# mapesynth_2pag.net
KiCad netlist of a schematic drawn in EAGLE
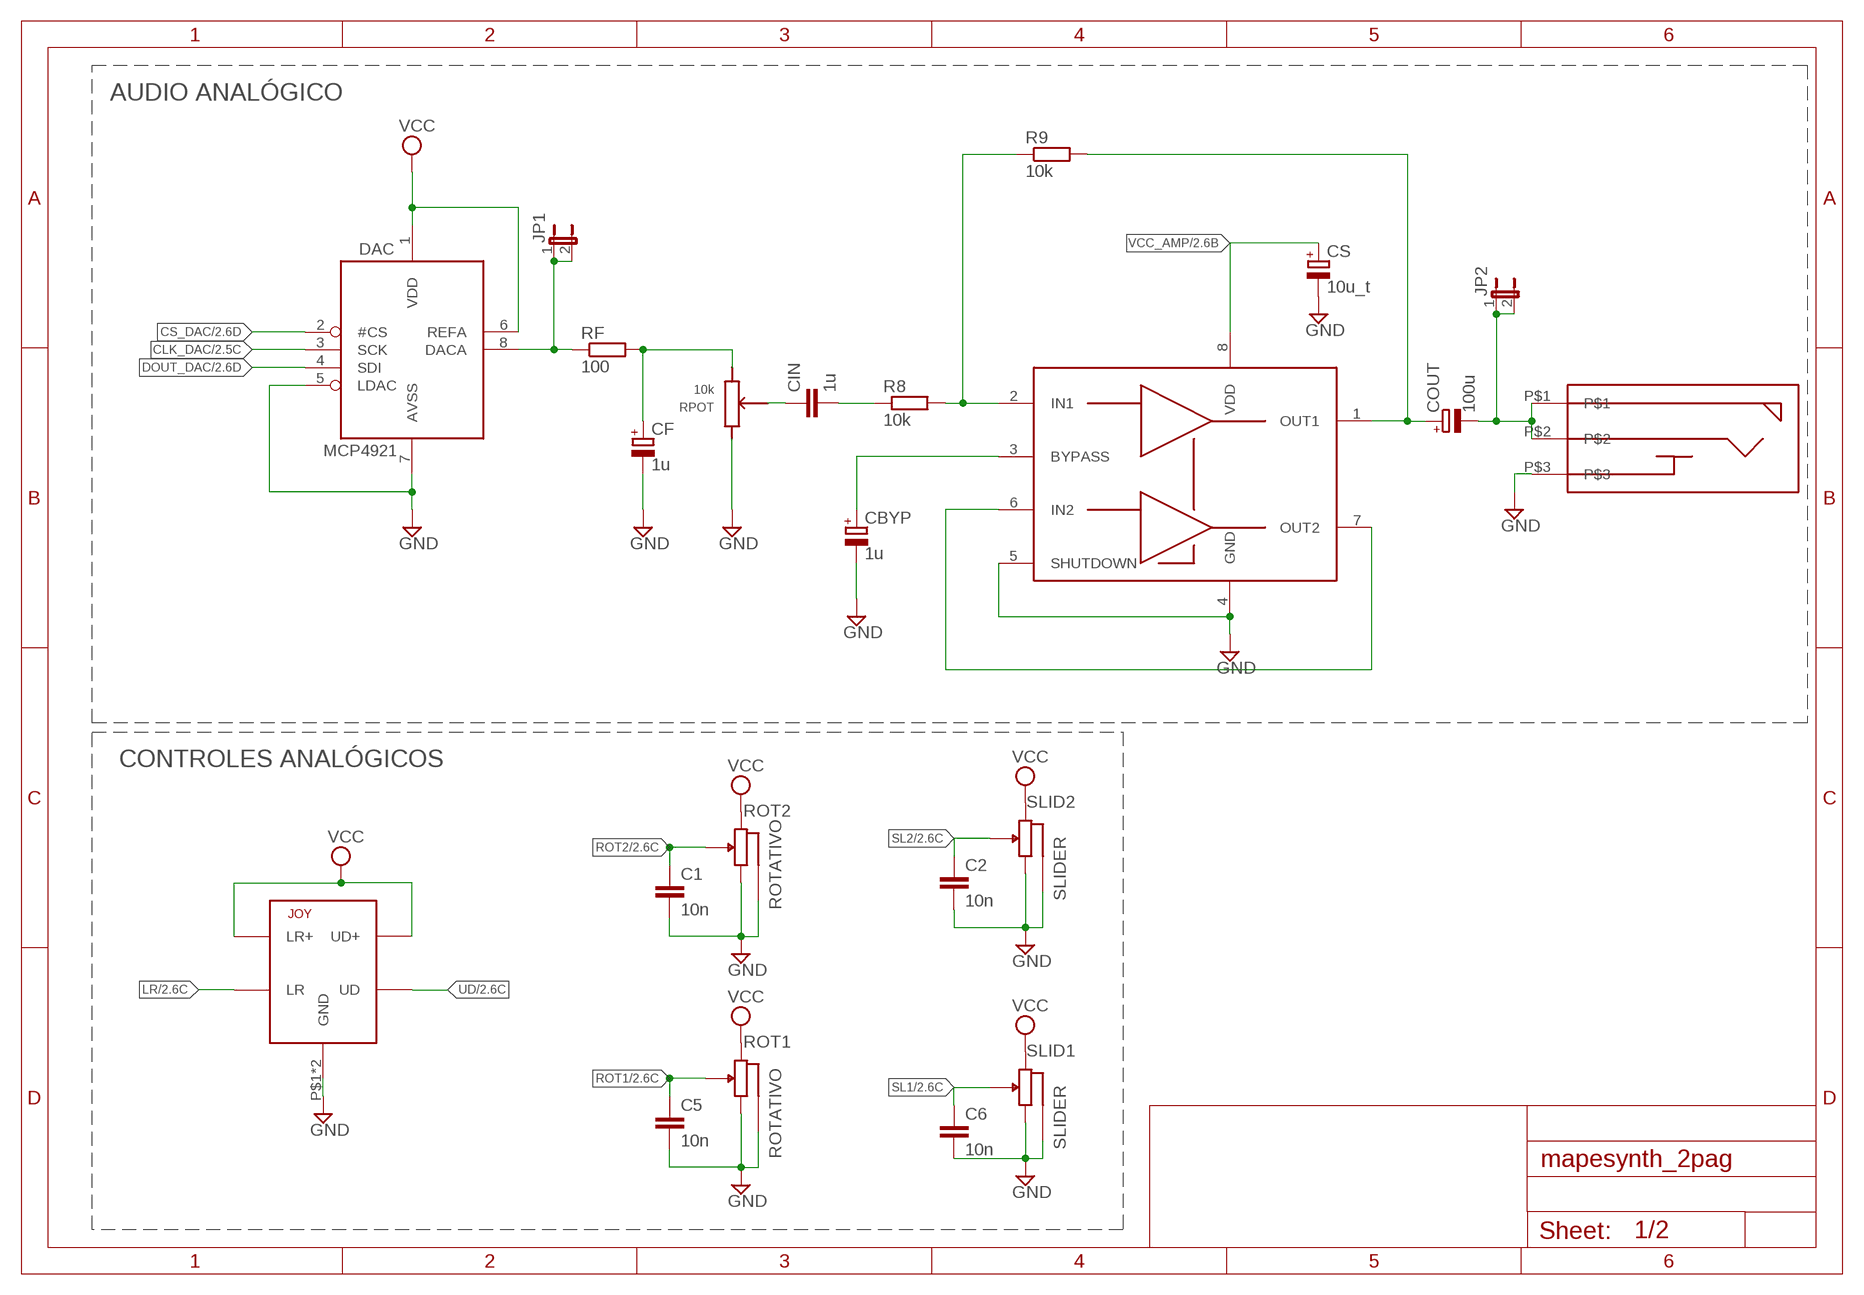
[diagram p0: schematic, sheet 1]
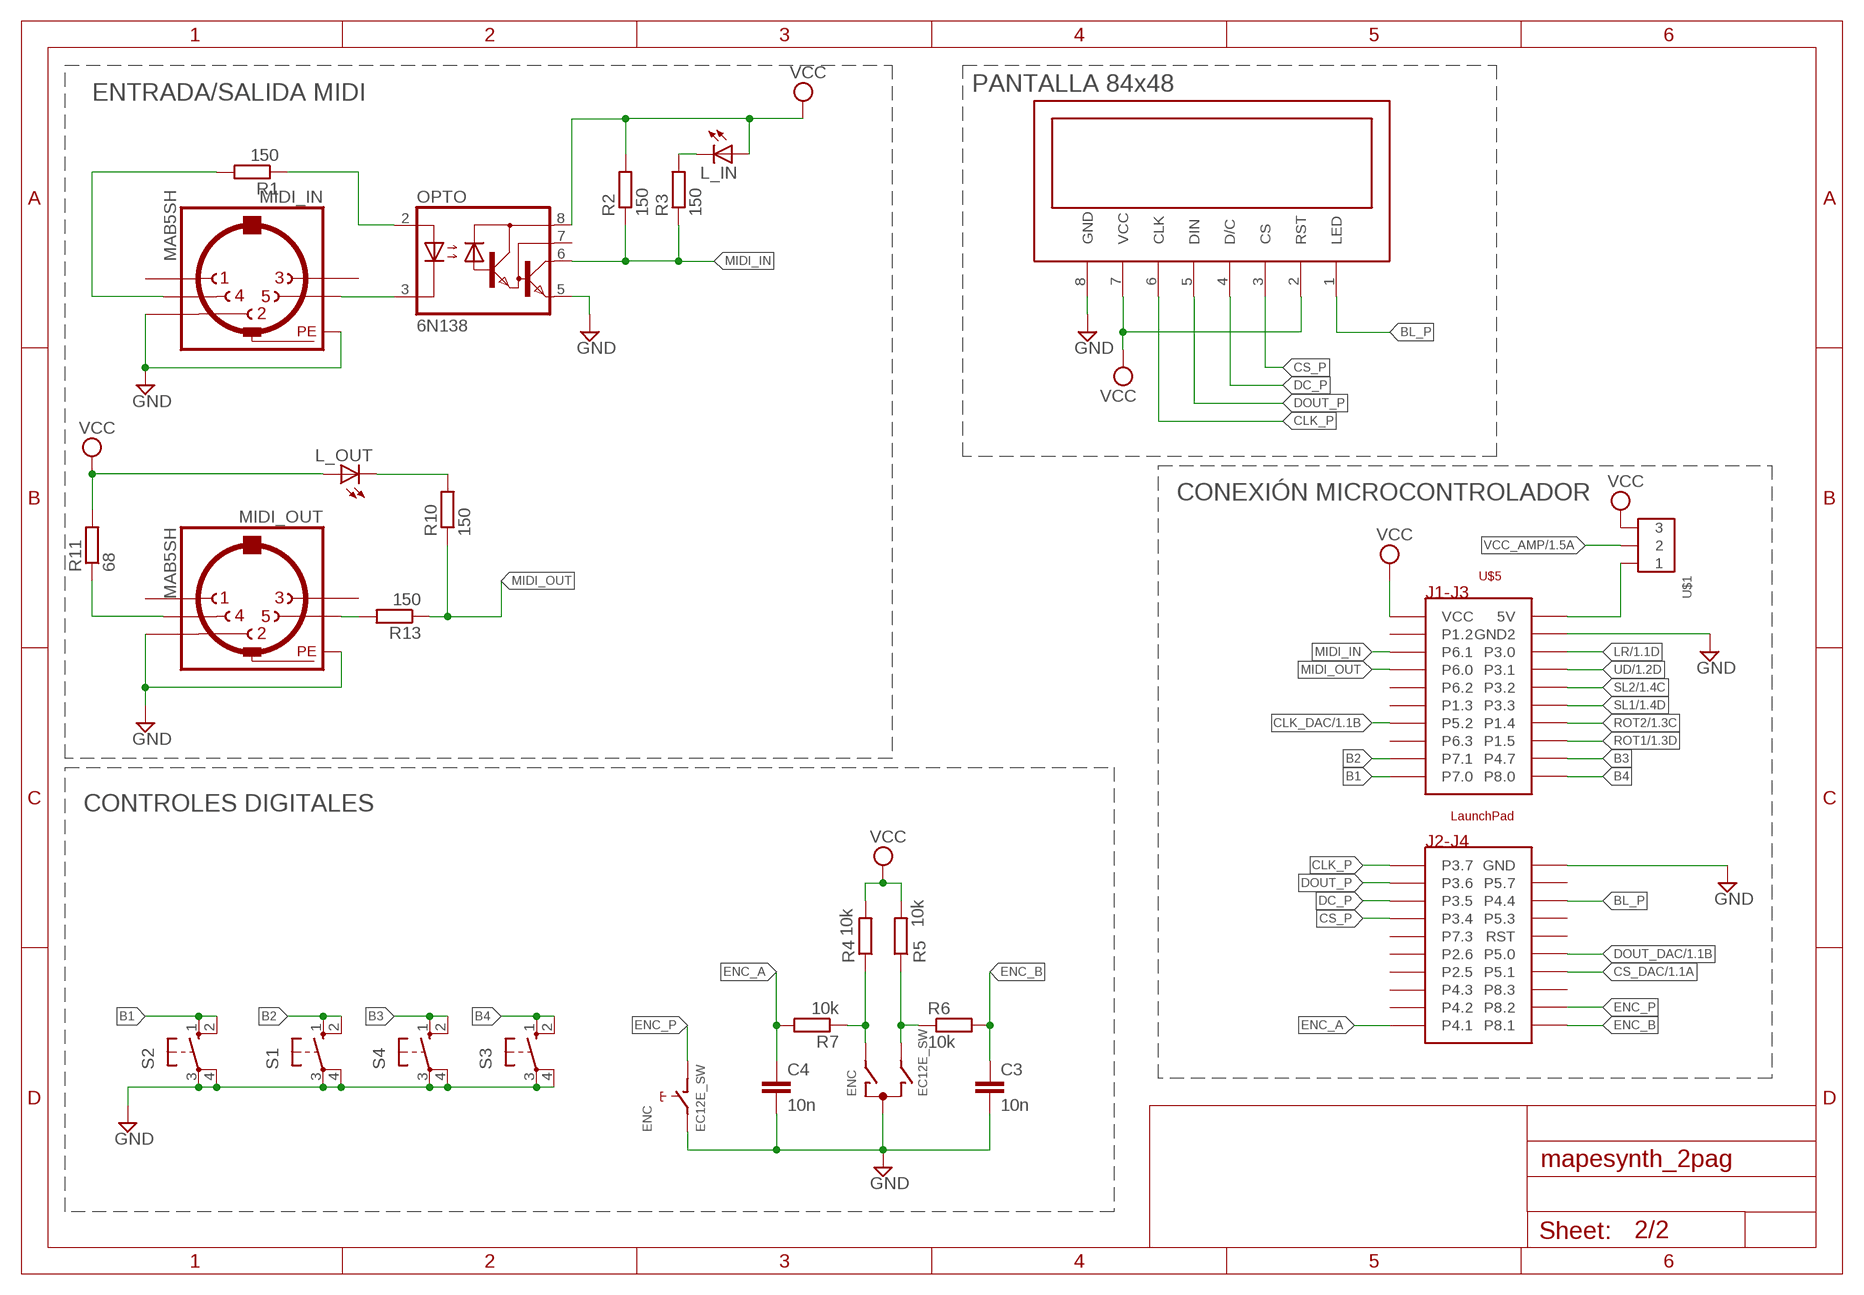
[diagram p1: schematic, sheet 2]

(export (version "E")
  (design (tool "Eeschema 10.0.6"))
  (components
    (comp (ref "C3")
      (value "10n")
      (footprint "eagle-import:C050-024X044")
      (libsource (lib "eagle-import") (part "rcl_C-EU050-024X044"))
    )
    (comp (ref "C4")
      (value "10n")
      (footprint "eagle-import:C050-024X044")
      (libsource (lib "eagle-import") (part "rcl_C-EU050-024X044"))
    )
    (comp (ref "ENC")
      (value "EC12E_SW")
      (footprint "eagle-import:ALPS_EC12E_SW")
      (fields (field (name "MPN") "EC12E2424407"))
      (libsource (lib "eagle-import") (part "EC12E_SW"))
    )
    (comp (ref "L_IN")
      (value "LED5MM")
      (footprint "eagle-import:LED5MM")
      (libsource (lib "eagle-import") (part "LED5MM"))
    )
    (comp (ref "L_OUT")
      (value "LED5MM")
      (footprint "eagle-import:LED5MM")
      (libsource (lib "eagle-import") (part "LED5MM"))
    )
    (comp (ref "MIDI_IN")
      (value "MAB5SH")
      (footprint "eagle-import:MAB5SH")
      (libsource (lib "eagle-import") (part "MAB5SH"))
    )
    (comp (ref "MIDI_OUT")
      (value "MAB5SH")
      (footprint "eagle-import:MAB5SH")
      (libsource (lib "eagle-import") (part "MAB5SH"))
    )
    (comp (ref "OPTO")
      (value "6N138")
      (footprint "eagle-import:DIL08")
      (fields (field (name "MF") "VISHAY/TELEFUNKEN"))
      (libsource (lib "eagle-import") (part "6N138"))
    )
    (comp (ref "R1")
      (value "150")
      (footprint "eagle-import:0207_10")
      (libsource (lib "eagle-import") (part "resistor_R-EU_0207/10"))
    )
    (comp (ref "R2")
      (value "150")
      (footprint "eagle-import:0207_10")
      (libsource (lib "eagle-import") (part "resistor_R-EU_0207/10"))
    )
    (comp (ref "R3")
      (value "150")
      (footprint "eagle-import:0207_10")
      (libsource (lib "eagle-import") (part "resistor_R-EU_0207/10"))
    )
    (comp (ref "R4")
      (value "10k")
      (footprint "eagle-import:R1206")
      (libsource (lib "eagle-import") (part "R-EU_R1206"))
    )
    (comp (ref "R5")
      (value "10k")
      (footprint "eagle-import:R1206")
      (libsource (lib "eagle-import") (part "R-EU_R1206"))
    )
    (comp (ref "R6")
      (value "10k")
      (footprint "eagle-import:R1206")
      (libsource (lib "eagle-import") (part "R-EU_R1206"))
    )
    (comp (ref "R7")
      (value "10k")
      (footprint "eagle-import:R1206")
      (libsource (lib "eagle-import") (part "R-EU_R1206"))
    )
    (comp (ref "R10")
      (value "150")
      (footprint "eagle-import:0207_10")
      (libsource (lib "eagle-import") (part "resistor_R-EU_0207/10"))
    )
    (comp (ref "R11")
      (value "68")
      (footprint "eagle-import:0207_10")
      (libsource (lib "eagle-import") (part "resistor_R-EU_0207/10"))
    )
    (comp (ref "R13")
      (value "150")
      (footprint "eagle-import:0207_10")
      (libsource (lib "eagle-import") (part "resistor_R-EU_0207/10"))
    )
    (comp (ref "S1")
      (value "40-XX")
      (footprint "eagle-import:B3F-40XX")
      (fields (field (name "MF") "OMRON COMPONENTS USA") (field (name "MPN") "B3F-4000"))
      (libsource (lib "eagle-import") (part "40-XX"))
    )
    (comp (ref "S2")
      (value "40-XX")
      (footprint "eagle-import:B3F-40XX")
      (fields (field (name "MF") "OMRON COMPONENTS USA") (field (name "MPN") "B3F-4000"))
      (libsource (lib "eagle-import") (part "40-XX"))
    )
    (comp (ref "S3")
      (value "40-XX")
      (footprint "eagle-import:B3F-40XX")
      (fields (field (name "MF") "OMRON COMPONENTS USA") (field (name "MPN") "B3F-4000"))
      (libsource (lib "eagle-import") (part "40-XX"))
    )
    (comp (ref "S4")
      (value "40-XX")
      (footprint "eagle-import:B3F-40XX")
      (fields (field (name "MF") "OMRON COMPONENTS USA") (field (name "MPN") "B3F-4000"))
      (libsource (lib "eagle-import") (part "40-XX"))
    )
    (comp (ref "U$1")
      (value "JP3")
      (footprint "eagle-import:JP3")
      (libsource (lib "eagle-import") (part "JP3"))
    )
    (comp (ref "U$3")
      (value "NOKIA_5110")
      (footprint "eagle-import:NOKIA_5110")
      (libsource (lib "eagle-import") (part "NOKIA_5110"))
    )
    (comp (ref "U$5")
      (value "LAUNCHPAD_XL")
      (footprint "eagle-import:LAUNCHPAD_XL")
      (libsource (lib "eagle-import") (part "LAUNCHPAD_XL"))
    )
    (comp (ref "AMP")
      (value "TPA6111")
      (footprint "eagle-import:SO-08")
      (libsource (lib "eagle-import") (part "TPA6111"))
    )
    (comp (ref "C1")
      (value "10n")
      (footprint "eagle-import:C050-024X044")
      (libsource (lib "eagle-import") (part "rcl_C-EU050-024X044"))
    )
    (comp (ref "C2")
      (value "10n")
      (footprint "eagle-import:C050-024X044")
      (libsource (lib "eagle-import") (part "rcl_C-EU050-024X044"))
    )
    (comp (ref "C5")
      (value "10n")
      (footprint "eagle-import:C050-024X044")
      (libsource (lib "eagle-import") (part "rcl_C-EU050-024X044"))
    )
    (comp (ref "C6")
      (value "10n")
      (footprint "eagle-import:C050-024X044")
      (libsource (lib "eagle-import") (part "rcl_C-EU050-024X044"))
    )
    (comp (ref "CBYP")
      (value "1u")
      (footprint "eagle-import:153CLV-0405")
      (libsource (lib "eagle-import") (part "CPOL-EU153CLV-0405"))
    )
    (comp (ref "CF")
      (value "1u")
      (footprint "eagle-import:153CLV-0405")
      (libsource (lib "eagle-import") (part "CPOL-EU153CLV-0405"))
    )
    (comp (ref "CIN")
      (value "1u")
      (footprint "eagle-import:C1206")
      (libsource (lib "eagle-import") (part "C-EUC1206"))
    )
    (comp (ref "COUT")
      (value "100u")
      (footprint "eagle-import:153CLV-0605")
      (libsource (lib "eagle-import") (part "CPOL-EU153CLV-0605"))
    )
    (comp (ref "CS")
      (value "10u_t")
      (footprint "eagle-import:CT3528")
      (libsource (lib "eagle-import") (part "CPOL-EUCT3528"))
    )
    (comp (ref "DAC")
      (value "MCP4921EN_SMD")
      (footprint "eagle-import:SO-08")
      (libsource (lib "eagle-import") (part "MCP4921EN_SMD"))
    )
    (comp (ref "JOY")
      (value "JOYSTICK")
      (footprint "eagle-import:PLACAJSTICK")
      (libsource (lib "eagle-import") (part "JOYSTICK"))
    )
    (comp (ref "JP1")
      (value "JP1E")
      (footprint "eagle-import:JP1")
      (libsource (lib "eagle-import") (part "JP1E"))
    )
    (comp (ref "JP2")
      (value "JP1E")
      (footprint "eagle-import:JP1")
      (libsource (lib "eagle-import") (part "JP1E"))
    )
    (comp (ref "R8")
      (value "10k")
      (footprint "eagle-import:M1206")
      (libsource (lib "eagle-import") (part "rcl_R-EU_M1206"))
    )
    (comp (ref "R9")
      (value "10k")
      (footprint "eagle-import:M1206")
      (libsource (lib "eagle-import") (part "rcl_R-EU_M1206"))
    )
    (comp (ref "RF")
      (value "100")
      (footprint "eagle-import:M1206")
      (libsource (lib "eagle-import") (part "rcl_R-EU_M1206"))
    )
    (comp (ref "ROT1")
      (value "ROTATIVO")
      (footprint "eagle-import:ROTATIVO")
      (libsource (lib "eagle-import") (part "ROTATIVO"))
    )
    (comp (ref "ROT2")
      (value "ROTATIVO")
      (footprint "eagle-import:ROTATIVO")
      (libsource (lib "eagle-import") (part "ROTATIVO"))
    )
    (comp (ref "RPOT")
      (value "10k")
      (footprint "eagle-import:POT_VOL")
      (libsource (lib "eagle-import") (part "POT_VOL"))
    )
    (comp (ref "SLID1")
      (value "SLIDER")
      (footprint "eagle-import:SLIDER")
      (libsource (lib "eagle-import") (part "SLIDER"))
    )
    (comp (ref "SLID2")
      (value "SLIDER")
      (footprint "eagle-import:SLIDER")
      (libsource (lib "eagle-import") (part "SLIDER"))
    )
    (comp (ref "U$4")
      (value "JACK_3_5MM_VA")
      (footprint "eagle-import:JACK3_5MM_V2")
      (libsource (lib "eagle-import") (part "JACK_3_5MM_VA"))
    )
  )
  (nets
    (net (code "1") (name "B1") (class "Default")
      (node (ref "S2") (pin "1") (pinfunction "S_1") (pintype "passive"))
      (node (ref "S2") (pin "2") (pinfunction "S1_2") (pintype "passive"))
      (node (ref "U$5") (pin "P$10") (pinfunction "P7.0_P$10") (pintype "bidirectional"))
    )
    (net (code "2") (name "B2") (class "Default")
      (node (ref "S1") (pin "1") (pinfunction "S_1") (pintype "passive"))
      (node (ref "S1") (pin "2") (pinfunction "S1_2") (pintype "passive"))
      (node (ref "U$5") (pin "P$9") (pinfunction "P7.1_P$9") (pintype "bidirectional"))
    )
    (net (code "3") (name "B3") (class "Default")
      (node (ref "S4") (pin "1") (pinfunction "S_1") (pintype "passive"))
      (node (ref "S4") (pin "2") (pinfunction "S1_2") (pintype "passive"))
      (node (ref "U$5") (pin "P$29") (pinfunction "P4.7_P$29") (pintype "bidirectional"))
    )
    (net (code "4") (name "B4") (class "Default")
      (node (ref "S3") (pin "1") (pinfunction "S_1") (pintype "passive"))
      (node (ref "S3") (pin "2") (pinfunction "S1_2") (pintype "passive"))
      (node (ref "U$5") (pin "P$30") (pinfunction "P8.0_P$30") (pintype "bidirectional"))
    )
    (net (code "5") (name "BL_P") (class "Default")
      (node (ref "U$3") (pin "1") (pinfunction "LED_1") (pintype "bidirectional"))
      (node (ref "U$5") (pin "P$18") (pinfunction "P4.4_P$18") (pintype "bidirectional"))
    )
    (net (code "6") (name "CLK_DAC") (class "Default")
      (node (ref "DAC") (pin "3") (pinfunction "SCK_3") (pintype "input"))
      (node (ref "U$5") (pin "P$7") (pinfunction "P5.2_P$7") (pintype "bidirectional"))
    )
    (net (code "7") (name "CLK_P") (class "Default")
      (node (ref "U$3") (pin "6") (pinfunction "CLK_6") (pintype "bidirectional"))
      (node (ref "U$5") (pin "P$40") (pinfunction "P3.7_P$40") (pintype "bidirectional"))
    )
    (net (code "8") (name "CS_DAC") (class "Default")
      (node (ref "DAC") (pin "2") (pinfunction "#CS_2") (pintype "input"))
      (node (ref "U$5") (pin "P$14") (pinfunction "P5.1_P$14") (pintype "bidirectional"))
    )
    (net (code "9") (name "CS_P") (class "Default")
      (node (ref "U$3") (pin "3") (pinfunction "CS_3") (pintype "bidirectional"))
      (node (ref "U$5") (pin "P$37") (pinfunction "P3.4_P$37") (pintype "bidirectional"))
    )
    (net (code "10") (name "DC_P") (class "Default")
      (node (ref "U$3") (pin "4") (pinfunction "D/C_4") (pintype "bidirectional"))
      (node (ref "U$5") (pin "P$38") (pinfunction "P3.5_P$38") (pintype "bidirectional"))
    )
    (net (code "11") (name "DOUT_DAC") (class "Default")
      (node (ref "DAC") (pin "4") (pinfunction "SDI_4") (pintype "input"))
      (node (ref "U$5") (pin "P$15") (pinfunction "P5.0_P$15") (pintype "bidirectional"))
    )
    (net (code "12") (name "DOUT_P") (class "Default")
      (node (ref "U$3") (pin "5") (pinfunction "DIN_5") (pintype "bidirectional"))
      (node (ref "U$5") (pin "P$39") (pinfunction "P3.6_P$39") (pintype "bidirectional"))
    )
    (net (code "13") (name "ENC_A") (class "Default")
      (node (ref "C4") (pin "1") (pinfunction "1_1") (pintype "passive"))
      (node (ref "R7") (pin "2") (pinfunction "2_2") (pintype "passive"))
      (node (ref "U$5") (pin "P$31") (pinfunction "P4.1_P$31") (pintype "bidirectional"))
    )
    (net (code "14") (name "ENC_B") (class "Default")
      (node (ref "C3") (pin "1") (pinfunction "1_1") (pintype "passive"))
      (node (ref "R6") (pin "2") (pinfunction "2_2") (pintype "passive"))
      (node (ref "U$5") (pin "P$11") (pinfunction "P8.1_P$11") (pintype "bidirectional"))
    )
    (net (code "15") (name "ENC_P") (class "Default")
      (node (ref "ENC") (pin "D") (pinfunction "1_D") (pintype "passive"))
      (node (ref "U$5") (pin "P$12") (pinfunction "P8.2_P$12") (pintype "bidirectional"))
    )
    (net (code "16") (name "GND") (class "Default")
      (node (ref "AMP") (pin "4") (pinfunction "GND_4") (pintype "bidirectional"))
      (node (ref "AMP") (pin "5") (pinfunction "SHUTDOWN_5") (pintype "bidirectional"))
      (node (ref "C1") (pin "2") (pinfunction "2_2") (pintype "passive"))
      (node (ref "C2") (pin "2") (pinfunction "2_2") (pintype "passive"))
      (node (ref "C3") (pin "2") (pinfunction "2_2") (pintype "passive"))
      (node (ref "C4") (pin "2") (pinfunction "2_2") (pintype "passive"))
      (node (ref "C5") (pin "2") (pinfunction "2_2") (pintype "passive"))
      (node (ref "C6") (pin "2") (pinfunction "2_2") (pintype "passive"))
      (node (ref "CBYP") (pin "-") (pinfunction "-_-") (pintype "passive"))
      (node (ref "CF") (pin "-") (pinfunction "-_-") (pintype "passive"))
      (node (ref "CS") (pin "-") (pinfunction "-_-") (pintype "passive"))
      (node (ref "DAC") (pin "5") (pinfunction "LDAC_5") (pintype "input"))
      (node (ref "DAC") (pin "7") (pinfunction "AVSS_7") (pintype "power_in"))
      (node (ref "ENC") (pin "C") (pinfunction "C_C") (pintype "passive"))
      (node (ref "ENC") (pin "E") (pinfunction "2_E") (pintype "passive"))
      (node (ref "JOY") (pin "P$1") (pinfunction "GND_P$1") (pintype "bidirectional"))
      (node (ref "JOY") (pin "P$8") (pinfunction "GND_P$8") (pintype "bidirectional"))
      (node (ref "MIDI_IN") (pin "2") (pinfunction "2_2") (pintype "passive"))
      (node (ref "MIDI_IN") (pin "PE") (pinfunction "PE_PE") (pintype "power_in"))
      (node (ref "MIDI_IN") (pin "PE@") (pinfunction "PE_PE@") (pintype "power_in"))
      (node (ref "MIDI_OUT") (pin "2") (pinfunction "2_2") (pintype "passive"))
      (node (ref "MIDI_OUT") (pin "PE") (pinfunction "PE_PE") (pintype "power_in"))
      (node (ref "MIDI_OUT") (pin "PE@") (pinfunction "PE_PE@") (pintype "power_in"))
      (node (ref "OPTO") (pin "5") (pinfunction "GND_5") (pintype "passive"))
      (node (ref "ROT1") (pin "A") (pinfunction "1_A") (pintype "passive"))
      (node (ref "ROT1") (pin "GND1") (pinfunction "GND_GND1") (pintype "bidirectional"))
      (node (ref "ROT1") (pin "GND2") (pinfunction "GND_GND2") (pintype "bidirectional"))
      (node (ref "ROT2") (pin "A") (pinfunction "1_A") (pintype "passive"))
      (node (ref "ROT2") (pin "GND1") (pinfunction "GND_GND1") (pintype "bidirectional"))
      (node (ref "ROT2") (pin "GND2") (pinfunction "GND_GND2") (pintype "bidirectional"))
      (node (ref "RPOT") (pin "P$1") (pinfunction "P$1_P$1") (pintype "bidirectional"))
      (node (ref "S1") (pin "3") (pinfunction "P_3") (pintype "passive"))
      (node (ref "S1") (pin "4") (pinfunction "P1_4") (pintype "passive"))
      (node (ref "S2") (pin "3") (pinfunction "P_3") (pintype "passive"))
      (node (ref "S2") (pin "4") (pinfunction "P1_4") (pintype "passive"))
      (node (ref "S3") (pin "3") (pinfunction "P_3") (pintype "passive"))
      (node (ref "S3") (pin "4") (pinfunction "P1_4") (pintype "passive"))
      (node (ref "S4") (pin "3") (pinfunction "P_3") (pintype "passive"))
      (node (ref "S4") (pin "4") (pinfunction "P1_4") (pintype "passive"))
      (node (ref "SLID1") (pin "1") (pinfunction "1_1") (pintype "passive"))
      (node (ref "SLID1") (pin "4") (pinfunction "GND_4") (pintype "bidirectional"))
      (node (ref "SLID1") (pin "5") (pinfunction "GND_5") (pintype "bidirectional"))
      (node (ref "SLID1") (pin "6") (pinfunction "GND_6") (pintype "bidirectional"))
      (node (ref "SLID1") (pin "7") (pinfunction "GND_7") (pintype "bidirectional"))
      (node (ref "SLID2") (pin "1") (pinfunction "1_1") (pintype "passive"))
      (node (ref "SLID2") (pin "4") (pinfunction "GND_4") (pintype "bidirectional"))
      (node (ref "SLID2") (pin "5") (pinfunction "GND_5") (pintype "bidirectional"))
      (node (ref "SLID2") (pin "6") (pinfunction "GND_6") (pintype "bidirectional"))
      (node (ref "SLID2") (pin "7") (pinfunction "GND_7") (pintype "bidirectional"))
      (node (ref "U$3") (pin "8") (pinfunction "GND_8") (pintype "bidirectional"))
      (node (ref "U$4") (pin "P$3") (pinfunction "P$3_P$3") (pintype "bidirectional"))
      (node (ref "U$5") (pin "P$20") (pinfunction "GND_P$20") (pintype "bidirectional"))
      (node (ref "U$5") (pin "P$22") (pinfunction "GND2_P$22") (pintype "bidirectional"))
    )
    (net (code "17") (name "LR") (class "Default")
      (node (ref "JOY") (pin "P$3") (pinfunction "LR_P$3") (pintype "bidirectional"))
      (node (ref "JOY") (pin "P$6") (pinfunction "LR_P$6") (pintype "bidirectional"))
      (node (ref "U$5") (pin "P$23") (pinfunction "P3.0_P$23") (pintype "bidirectional"))
    )
    (net (code "18") (name "MIDI_IN") (class "Default")
      (node (ref "OPTO") (pin "6") (pinfunction "VO_6") (pintype "passive"))
      (node (ref "R2") (pin "1") (pinfunction "1_1") (pintype "passive"))
      (node (ref "R3") (pin "1") (pinfunction "1_1") (pintype "passive"))
      (node (ref "U$5") (pin "P$3") (pinfunction "P6.1_P$3") (pintype "bidirectional"))
    )
    (net (code "19") (name "MIDI_OUT") (class "Default")
      (node (ref "R10") (pin "1") (pinfunction "1_1") (pintype "passive"))
      (node (ref "R13") (pin "1") (pinfunction "1_1") (pintype "passive"))
      (node (ref "U$5") (pin "P$4") (pinfunction "P6.0_P$4") (pintype "bidirectional"))
    )
    (net (code "20") (name "Net-(AMP-BYPASS)") (class "Default")
      (node (ref "AMP") (pin "3") (pinfunction "BYPASS_3") (pintype "bidirectional"))
      (node (ref "CBYP") (pin "+") (pinfunction "+_+") (pintype "passive"))
    )
    (net (code "21") (name "Net-(AMP-IN1)") (class "Default")
      (node (ref "AMP") (pin "2") (pinfunction "IN1_2") (pintype "bidirectional"))
      (node (ref "R8") (pin "2") (pinfunction "2_2") (pintype "passive"))
      (node (ref "R9") (pin "1") (pinfunction "1_1") (pintype "passive"))
    )
    (net (code "22") (name "Net-(AMP-IN2)") (class "Default")
      (node (ref "AMP") (pin "6") (pinfunction "IN2_6") (pintype "bidirectional"))
      (node (ref "AMP") (pin "7") (pinfunction "OUT2_7") (pintype "bidirectional"))
    )
    (net (code "23") (name "Net-(AMP-OUT1)") (class "Default")
      (node (ref "AMP") (pin "1") (pinfunction "OUT1_1") (pintype "bidirectional"))
      (node (ref "COUT") (pin "+") (pinfunction "+_+") (pintype "passive"))
      (node (ref "R9") (pin "2") (pinfunction "2_2") (pintype "passive"))
    )
    (net (code "24") (name "Net-(CF-Pad+)") (class "Default")
      (node (ref "CF") (pin "+") (pinfunction "+_+") (pintype "passive"))
      (node (ref "RF") (pin "2") (pinfunction "2_2") (pintype "passive"))
      (node (ref "RPOT") (pin "P$3") (pinfunction "P$3_P$3") (pintype "bidirectional"))
    )
    (net (code "25") (name "Net-(CIN-Pad1)") (class "Default")
      (node (ref "CIN") (pin "1") (pinfunction "1_1") (pintype "passive"))
      (node (ref "RPOT") (pin "P$2") (pinfunction "P$2_P$2") (pintype "bidirectional"))
    )
    (net (code "26") (name "Net-(CIN-Pad2)") (class "Default")
      (node (ref "CIN") (pin "2") (pinfunction "2_2") (pintype "passive"))
      (node (ref "R8") (pin "1") (pinfunction "1_1") (pintype "passive"))
    )
    (net (code "27") (name "Net-(COUT-Pad-)") (class "Default")
      (node (ref "COUT") (pin "-") (pinfunction "-_-") (pintype "passive"))
      (node (ref "JP2") (pin "1") (pinfunction "1_1") (pintype "passive"))
      (node (ref "JP2") (pin "2") (pinfunction "2_2") (pintype "passive"))
      (node (ref "U$4") (pin "P$1") (pinfunction "P$1_P$1") (pintype "bidirectional"))
      (node (ref "U$4") (pin "P$2") (pinfunction "P$2_P$2") (pintype "bidirectional"))
    )
    (net (code "28") (name "Net-(DAC-DACA)") (class "Default")
      (node (ref "DAC") (pin "8") (pinfunction "DACA_8") (pintype "output"))
      (node (ref "JP1") (pin "1") (pinfunction "1_1") (pintype "passive"))
      (node (ref "JP1") (pin "2") (pinfunction "2_2") (pintype "passive"))
      (node (ref "RF") (pin "1") (pinfunction "1_1") (pintype "passive"))
    )
    (net (code "29") (name "Net-(ENC-PadA)") (class "Default")
      (node (ref "ENC") (pin "A") (pinfunction "A_A") (pintype "passive"))
      (node (ref "R4") (pin "1") (pinfunction "1_1") (pintype "passive"))
      (node (ref "R7") (pin "1") (pinfunction "1_1") (pintype "passive"))
    )
    (net (code "30") (name "Net-(ENC-PadB)") (class "Default")
      (node (ref "ENC") (pin "B") (pinfunction "B_B") (pintype "passive"))
      (node (ref "R5") (pin "1") (pinfunction "1_1") (pintype "passive"))
      (node (ref "R6") (pin "1") (pinfunction "1_1") (pintype "passive"))
    )
    (net (code "31") (name "Net-(L_IN-C)") (class "Default")
      (node (ref "L_IN") (pin "K") (pinfunction "C_K") (pintype "passive"))
      (node (ref "R3") (pin "2") (pinfunction "2_2") (pintype "passive"))
    )
    (net (code "32") (name "Net-(L_OUT-C)") (class "Default")
      (node (ref "L_OUT") (pin "K") (pinfunction "C_K") (pintype "passive"))
      (node (ref "R10") (pin "2") (pinfunction "2_2") (pintype "passive"))
    )
    (net (code "33") (name "Net-(MIDI_IN-Pad4)") (class "Default")
      (node (ref "MIDI_IN") (pin "4") (pinfunction "4_4") (pintype "passive"))
      (node (ref "R1") (pin "2") (pinfunction "2_2") (pintype "passive"))
    )
    (net (code "34") (name "Net-(MIDI_OUT-Pad4)") (class "Default")
      (node (ref "MIDI_OUT") (pin "4") (pinfunction "4_4") (pintype "passive"))
      (node (ref "R11") (pin "1") (pinfunction "1_1") (pintype "passive"))
    )
    (net (code "35") (name "Net-(MIDI_OUT-Pad5)") (class "Default")
      (node (ref "MIDI_OUT") (pin "5") (pinfunction "5_5") (pintype "passive"))
      (node (ref "R13") (pin "2") (pinfunction "2_2") (pintype "passive"))
    )
    (net (code "36") (name "Net-(OPTO-A)") (class "Default")
      (node (ref "OPTO") (pin "2") (pinfunction "A_2") (pintype "passive"))
      (node (ref "R1") (pin "1") (pinfunction "1_1") (pintype "passive"))
    )
    (net (code "37") (name "Net-(OPTO-C)") (class "Default")
      (node (ref "MIDI_IN") (pin "5") (pinfunction "5_5") (pintype "passive"))
      (node (ref "OPTO") (pin "3") (pinfunction "C_3") (pintype "passive"))
    )
    (net (code "38") (name "Net-(U$1-1)") (class "Default")
      (node (ref "U$1") (pin "P$1") (pinfunction "1_P$1") (pintype "bidirectional"))
      (node (ref "U$5") (pin "P$21") (pinfunction "5V_P$21") (pintype "bidirectional"))
    )
    (net (code "39") (name "ROT1") (class "Default")
      (node (ref "C5") (pin "1") (pinfunction "1_1") (pintype "passive"))
      (node (ref "ROT1") (pin "C") (pinfunction "2_C") (pintype "passive"))
      (node (ref "U$5") (pin "P$28") (pinfunction "P1.5_P$28") (pintype "bidirectional"))
    )
    (net (code "40") (name "ROT2") (class "Default")
      (node (ref "C1") (pin "1") (pinfunction "1_1") (pintype "passive"))
      (node (ref "ROT2") (pin "C") (pinfunction "2_C") (pintype "passive"))
      (node (ref "U$5") (pin "P$27") (pinfunction "P1.4_P$27") (pintype "bidirectional"))
    )
    (net (code "41") (name "SL1") (class "Default")
      (node (ref "C6") (pin "1") (pinfunction "1_1") (pintype "passive"))
      (node (ref "SLID1") (pin "2") (pinfunction "2_2") (pintype "passive"))
      (node (ref "U$5") (pin "P$26") (pinfunction "P3.3_P$26") (pintype "bidirectional"))
    )
    (net (code "42") (name "SL2") (class "Default")
      (node (ref "C2") (pin "1") (pinfunction "1_1") (pintype "passive"))
      (node (ref "SLID2") (pin "2") (pinfunction "2_2") (pintype "passive"))
      (node (ref "U$5") (pin "P$25") (pinfunction "P3.2_P$25") (pintype "bidirectional"))
    )
    (net (code "43") (name "UD") (class "Default")
      (node (ref "JOY") (pin "P$2") (pinfunction "UD_P$2") (pintype "bidirectional"))
      (node (ref "JOY") (pin "P$7") (pinfunction "UD_P$7") (pintype "bidirectional"))
      (node (ref "U$5") (pin "P$24") (pinfunction "P3.1_P$24") (pintype "bidirectional"))
    )
    (net (code "44") (name "VCC") (class "Default")
      (node (ref "DAC") (pin "1") (pinfunction "VDD_1") (pintype "power_in"))
      (node (ref "DAC") (pin "6") (pinfunction "REFA_6") (pintype "input"))
      (node (ref "JOY") (pin "P$4") (pinfunction "LR+_P$4") (pintype "bidirectional"))
      (node (ref "JOY") (pin "P$5") (pinfunction "UD+_P$5") (pintype "bidirectional"))
      (node (ref "L_IN") (pin "A") (pinfunction "A_A") (pintype "passive"))
      (node (ref "L_OUT") (pin "A") (pinfunction "A_A") (pintype "passive"))
      (node (ref "OPTO") (pin "8") (pinfunction "VCC_8") (pintype "passive"))
      (node (ref "R11") (pin "2") (pinfunction "2_2") (pintype "passive"))
      (node (ref "R2") (pin "2") (pinfunction "2_2") (pintype "passive"))
      (node (ref "R4") (pin "2") (pinfunction "2_2") (pintype "passive"))
      (node (ref "R5") (pin "2") (pinfunction "2_2") (pintype "passive"))
      (node (ref "ROT1") (pin "B") (pinfunction "3_B") (pintype "passive"))
      (node (ref "ROT2") (pin "B") (pinfunction "3_B") (pintype "passive"))
      (node (ref "SLID1") (pin "3") (pinfunction "3_3") (pintype "passive"))
      (node (ref "SLID2") (pin "3") (pinfunction "3_3") (pintype "passive"))
      (node (ref "U$1") (pin "P$3") (pinfunction "3_P$3") (pintype "bidirectional"))
      (node (ref "U$3") (pin "2") (pinfunction "RST_2") (pintype "bidirectional"))
      (node (ref "U$3") (pin "7") (pinfunction "VCC_7") (pintype "bidirectional"))
      (node (ref "U$5") (pin "P$1") (pinfunction "VCC_P$1") (pintype "bidirectional"))
    )
    (net (code "45") (name "VCC_AMP") (class "Default")
      (node (ref "AMP") (pin "8") (pinfunction "VDD_8") (pintype "bidirectional"))
      (node (ref "CS") (pin "+") (pinfunction "+_+") (pintype "passive"))
      (node (ref "U$1") (pin "P$2") (pinfunction "2_P$2") (pintype "bidirectional"))
    )
    (net (code "46") (name "unconnected-(MIDI_IN-Pad1)") (class "Default")
      (node (ref "MIDI_IN") (pin "1") (pinfunction "1_1") (pintype "passive"))
    )
    (net (code "47") (name "unconnected-(MIDI_IN-Pad3)") (class "Default")
      (node (ref "MIDI_IN") (pin "3") (pinfunction "3_3") (pintype "passive"))
    )
    (net (code "48") (name "unconnected-(MIDI_OUT-Pad1)") (class "Default")
      (node (ref "MIDI_OUT") (pin "1") (pinfunction "1_1") (pintype "passive"))
    )
    (net (code "49") (name "unconnected-(MIDI_OUT-Pad3)") (class "Default")
      (node (ref "MIDI_OUT") (pin "3") (pinfunction "3_3") (pintype "passive"))
    )
    (net (code "50") (name "unconnected-(OPTO-VB-Pad7)") (class "Default")
      (node (ref "OPTO") (pin "7") (pinfunction "VB_7") (pintype "passive"))
    )
    (net (code "51") (name "unconnected-(U$5-P1.2-PadP$2)") (class "Default")
      (node (ref "U$5") (pin "P$2") (pinfunction "P1.2_P$2") (pintype "bidirectional"))
    )
    (net (code "52") (name "unconnected-(U$5-P1.3-PadP$6)") (class "Default")
      (node (ref "U$5") (pin "P$6") (pinfunction "P1.3_P$6") (pintype "bidirectional"))
    )
    (net (code "53") (name "unconnected-(U$5-P2.5-PadP$34)") (class "Default")
      (node (ref "U$5") (pin "P$34") (pinfunction "P2.5_P$34") (pintype "bidirectional"))
    )
    (net (code "54") (name "unconnected-(U$5-P2.6-PadP$35)") (class "Default")
      (node (ref "U$5") (pin "P$35") (pinfunction "P2.6_P$35") (pintype "bidirectional"))
    )
    (net (code "55") (name "unconnected-(U$5-P4.2-PadP$32)") (class "Default")
      (node (ref "U$5") (pin "P$32") (pinfunction "P4.2_P$32") (pintype "bidirectional"))
    )
    (net (code "56") (name "unconnected-(U$5-P4.3-PadP$33)") (class "Default")
      (node (ref "U$5") (pin "P$33") (pinfunction "P4.3_P$33") (pintype "bidirectional"))
    )
    (net (code "57") (name "unconnected-(U$5-P5.3-PadP$17)") (class "Default")
      (node (ref "U$5") (pin "P$17") (pinfunction "P5.3_P$17") (pintype "bidirectional"))
    )
    (net (code "58") (name "unconnected-(U$5-P5.7-PadP$19)") (class "Default")
      (node (ref "U$5") (pin "P$19") (pinfunction "P5.7_P$19") (pintype "bidirectional"))
    )
    (net (code "59") (name "unconnected-(U$5-P6.2-PadP$5)") (class "Default")
      (node (ref "U$5") (pin "P$5") (pinfunction "P6.2_P$5") (pintype "bidirectional"))
    )
    (net (code "60") (name "unconnected-(U$5-P6.3-PadP$8)") (class "Default")
      (node (ref "U$5") (pin "P$8") (pinfunction "P6.3_P$8") (pintype "bidirectional"))
    )
    (net (code "61") (name "unconnected-(U$5-P7.3-PadP$36)") (class "Default")
      (node (ref "U$5") (pin "P$36") (pinfunction "P7.3_P$36") (pintype "bidirectional"))
    )
    (net (code "62") (name "unconnected-(U$5-P8.3-PadP$13)") (class "Default")
      (node (ref "U$5") (pin "P$13") (pinfunction "P8.3_P$13") (pintype "bidirectional"))
    )
    (net (code "63") (name "unconnected-(U$5-RST-PadP$16)") (class "Default")
      (node (ref "U$5") (pin "P$16") (pinfunction "RST_P$16") (pintype "bidirectional"))
    )
  )
)
